# sensor.net
KiCad netlist of a schematic drawn in Altium Designer
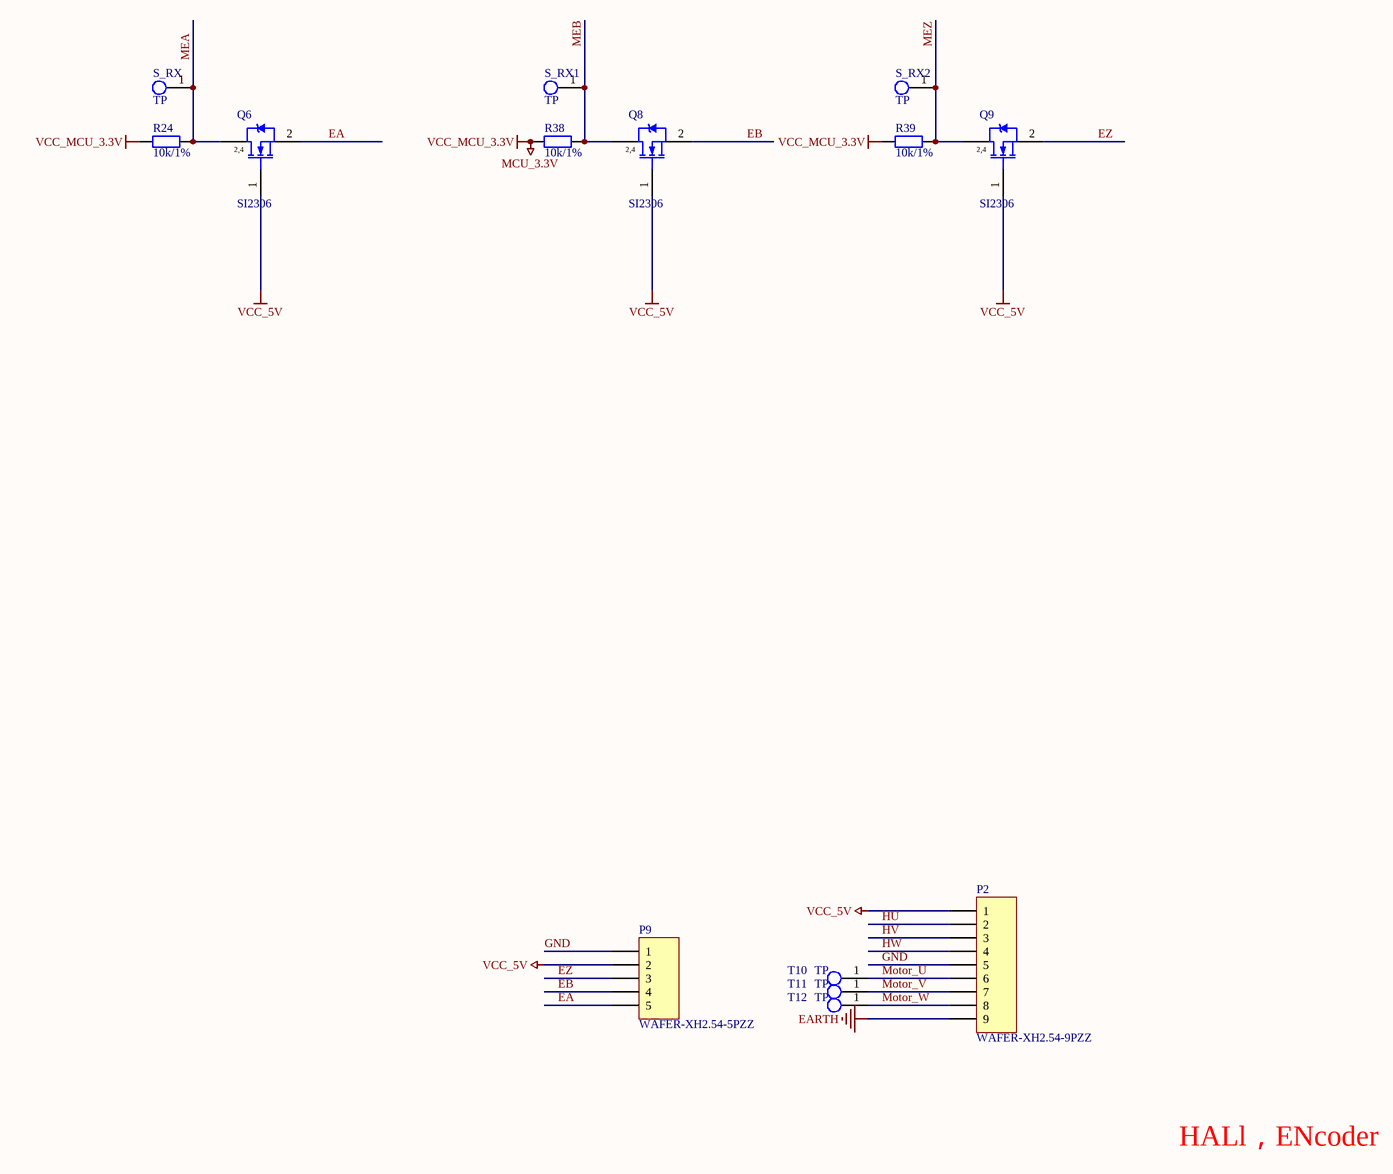
[diagram p0: sensor.SchDoc]

(export (version "E")
  (design (tool "Eeschema 10.0.6"))
  (components
    (comp (ref "P2")
      (value "WAFER-XH2.54-9PZZ")
      (footprint "XA2.5-9P")
      (description "Header, 9-Pin")
      (libsource (lib "Miscellaneous Connectors") (part "Header 9"))
    )
    (comp (ref "P9")
      (value "WAFER-XH2.54-5PZZ")
      (footprint "XA2.5-5P")
      (description "Header, 5-Pin")
      (libsource (lib "Miscellaneous Connectors") (part "Header 5"))
    )
    (comp (ref "Q6")
      (value "SI2306")
      (footprint "Pcblib_20110825:SOT23-3")
      (description "BUK92150-55A")
      (libsource (lib "Schlib1") (part "BUK92150-55A"))
    )
    (comp (ref "Q8")
      (value "SI2306")
      (footprint "SOT23-3")
      (description "BUK92150-55A")
      (libsource (lib "Schlib1") (part "BUK92150-55A"))
    )
    (comp (ref "Q9")
      (value "SI2306")
      (footprint "Pcblib_20110825:SOT23-3")
      (description "BUK92150-55A")
      (libsource (lib "Schlib1") (part "BUK92150-55A"))
    )
    (comp (ref "R24")
      (value "10k/1%")
      (footprint "Pcblib_20110825:0603R")
      (description "Resistor")
      (libsource (lib "Miscellaneous Devices") (part "Res2"))
    )
    (comp (ref "R38")
      (value "10k/1%")
      (footprint "Pcblib_20110825:0603R")
      (description "Resistor")
      (libsource (lib "Miscellaneous Devices") (part "Res2"))
    )
    (comp (ref "R39")
      (value "10k/1%")
      (footprint "Pcblib_20110825:0603R")
      (description "Resistor")
      (libsource (lib "Miscellaneous Devices") (part "Res2"))
    )
    (comp (ref "S_RX")
      (value "TP")
      (footprint "Pcblib_20110825:TPD")
      (libsource (lib "Schlib_20110825") (part "TP"))
    )
    (comp (ref "S_RX1")
      (value "TP")
      (footprint "Pcblib_20110825:TPD")
      (libsource (lib "Schlib_20110825") (part "TP"))
    )
    (comp (ref "S_RX2")
      (value "TP")
      (footprint "Pcblib_20110825:TPD")
      (libsource (lib "Schlib_20110825") (part "TP"))
    )
    (comp (ref "T10") (value "TP") (footprint "TPD") (libsource (lib "Schlib_20110825") (part "TP")))
    (comp (ref "T11") (value "TP") (footprint "TPD") (libsource (lib "Schlib_20110825") (part "TP")))
    (comp (ref "T12") (value "TP") (footprint "TPD") (libsource (lib "Schlib_20110825") (part "TP")))
  )
  (nets
    (net (code "1") (name "/EA") (class "Default")
      (node (ref "P9") (pin "5") (pinfunction "5_5") (pintype "passive"))
      (node (ref "Q6") (pin "2") (pinfunction "S_2") (pintype "passive"))
    )
    (net (code "2") (name "/EB") (class "Default")
      (node (ref "P9") (pin "4") (pinfunction "4_4") (pintype "passive"))
      (node (ref "Q8") (pin "2") (pinfunction "S_2") (pintype "passive"))
    )
    (net (code "3") (name "/EZ") (class "Default")
      (node (ref "P9") (pin "3") (pinfunction "3_3") (pintype "passive"))
      (node (ref "Q9") (pin "2") (pinfunction "S_2") (pintype "passive"))
    )
    (net (code "4") (name "/GND") (class "Default")
      (node (ref "P2") (pin "5") (pinfunction "5_5") (pintype "passive"))
      (node (ref "P9") (pin "1") (pinfunction "1_1") (pintype "passive"))
    )
    (net (code "5") (name "/HU") (class "Default")
      (node (ref "P2") (pin "2") (pinfunction "2_2") (pintype "passive"))
    )
    (net (code "6") (name "/HV") (class "Default")
      (node (ref "P2") (pin "3") (pinfunction "3_3") (pintype "passive"))
    )
    (net (code "7") (name "/HW") (class "Default")
      (node (ref "P2") (pin "4") (pinfunction "4_4") (pintype "passive"))
    )
    (net (code "8") (name "/MEA") (class "Default")
      (node (ref "Q6") (pin "3") (pinfunction "D_3") (pintype "passive"))
      (node (ref "R24") (pin "2") (pinfunction "2_2") (pintype "passive"))
      (node (ref "S_RX") (pin "1") (pintype "passive"))
    )
    (net (code "9") (name "/MEB") (class "Default")
      (node (ref "Q8") (pin "3") (pinfunction "D_3") (pintype "passive"))
      (node (ref "R38") (pin "2") (pinfunction "2_2") (pintype "passive"))
      (node (ref "S_RX1") (pin "1") (pintype "passive"))
    )
    (net (code "10") (name "/MEZ") (class "Default")
      (node (ref "Q9") (pin "3") (pinfunction "D_3") (pintype "passive"))
      (node (ref "R39") (pin "2") (pinfunction "2_2") (pintype "passive"))
      (node (ref "S_RX2") (pin "1") (pintype "passive"))
    )
    (net (code "11") (name "/Motor_U") (class "Default")
      (node (ref "P2") (pin "6") (pinfunction "6_6") (pintype "passive"))
      (node (ref "T10") (pin "1") (pintype "passive"))
    )
    (net (code "12") (name "/Motor_V") (class "Default")
      (node (ref "P2") (pin "7") (pinfunction "7_7") (pintype "passive"))
      (node (ref "T11") (pin "1") (pintype "passive"))
    )
    (net (code "13") (name "/Motor_W") (class "Default")
      (node (ref "P2") (pin "8") (pinfunction "8_8") (pintype "passive"))
      (node (ref "T12") (pin "1") (pintype "passive"))
    )
    (net (code "14") (name "EARTH") (class "Default")
      (node (ref "P2") (pin "9") (pinfunction "9_9") (pintype "passive"))
    )
    (net (code "15") (name "MCU_3.3V") (class "Default")
      (node (ref "R24") (pin "1") (pinfunction "1_1") (pintype "passive"))
      (node (ref "R38") (pin "1") (pinfunction "1_1") (pintype "passive"))
      (node (ref "R39") (pin "1") (pinfunction "1_1") (pintype "passive"))
    )
    (net (code "16") (name "VCC_5V") (class "Default")
      (node (ref "P2") (pin "1") (pinfunction "1_1") (pintype "passive"))
      (node (ref "P9") (pin "2") (pinfunction "2_2") (pintype "passive"))
      (node (ref "Q6") (pin "1") (pinfunction "G_1") (pintype "passive"))
      (node (ref "Q8") (pin "1") (pinfunction "G_1") (pintype "passive"))
      (node (ref "Q9") (pin "1") (pinfunction "G_1") (pintype "passive"))
    )
  )
)
